# SurfaceEEG_E_V1_1.net
KiCad netlist of a schematic drawn in EAGLE
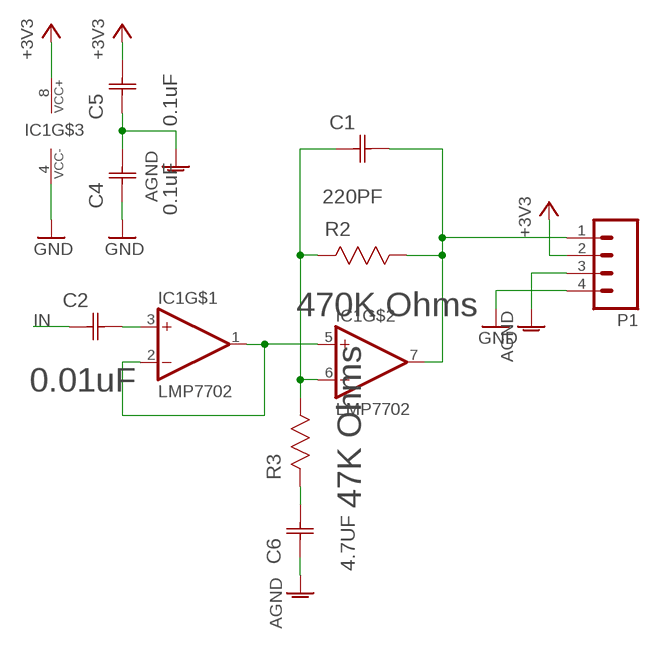
[diagram p0: schematic, sheet 1]

(export (version "E")
  (design (tool "Eeschema 10.0.6"))
  (components
    (comp (ref "C1")
      (value "220PF")
      (footprint "eagle-import:CAPC1608X90N")
      (fields (field (name "MPN") "0603ZC221KAT2A") (field (name "TOLERANCE") "±10%"))
      (libsource (lib "eagle-import") (part "0603ZC221KAT2A"))
    )
    (comp (ref "C2")
      (value "0.01uF")
      (footprint "eagle-import:CAPC1005X60N")
      (fields (field (name "MPN") "C0402C103J3RACTU") (field (name "TOLERANCE") "±5%"))
      (libsource (lib "eagle-import") (part "C0402C103J3RACTU"))
    )
    (comp (ref "C4")
      (value "0.1uF")
      (footprint "eagle-import:CAPC1005X60N")
      (fields (field (name "MPN") "04023C104KAT2A") (field (name "TOLERANCE") "±10%"))
      (libsource (lib "eagle-import") (part "04023C104KAT2A"))
    )
    (comp (ref "C5")
      (value "0.1uF")
      (footprint "eagle-import:CAPC1005X60N")
      (fields (field (name "MPN") "04023C104KAT2A") (field (name "TOLERANCE") "±10%"))
      (libsource (lib "eagle-import") (part "04023C104KAT2A"))
    )
    (comp (ref "C6")
      (value "4.7UF")
      (footprint "eagle-import:CAPC1608X90N")
      (fields (field (name "MPN") "06036D475MAT2A") (field (name "TOLERANCE") "±20%"))
      (libsource (lib "eagle-import") (part "06036D475MAT2A"))
    )
    (comp (ref "IC1")
      (value "LMP7702")
      (footprint "eagle-import:VSSOP8")
      (fields (field (name "MPN") "LMP7702MM/NOPB"))
      (libsource (lib "eagle-import") (part "LMP7702"))
    )
    (comp (ref "P1")
      (value "M04SMD")
      (footprint "eagle-import:1X04-SMD")
      (libsource (lib "eagle-import") (part "M04SMD"))
    )
    (comp (ref "R2")
      (value "470K Ohms")
      (footprint "eagle-import:RESC1608X60N")
      (fields (field (name "MPN") "RC0603FR-07470KL") (field (name "TOLERANCE") "±1%"))
      (libsource (lib "eagle-import") (part "RC0603FR-07470KL"))
    )
    (comp (ref "R3")
      (value "47K Ohms")
      (footprint "eagle-import:RESC1608X60N")
      (fields (field (name "MPN") "RC0603FR-0747KL") (field (name "TOLERANCE") "±1%"))
      (libsource (lib "eagle-import") (part "RC0603FR-0747KL"))
    )
  )
  (nets
    (net (code "1") (name "+3V3") (class "Default")
      (node (ref "C5") (pin "1") (pinfunction "C2_1") (pintype "passive"))
      (node (ref "IC1") (pin "8") (pinfunction "VCC+_8") (pintype "power_in"))
      (node (ref "P1") (pin "2") (pinfunction "2_2") (pintype "passive"))
    )
    (net (code "2") (name "/IN") (class "Default")
      (node (ref "C2") (pin "1") (pinfunction "C1_1") (pintype "passive"))
    )
    (net (code "3") (name "AGND") (class "Default")
      (node (ref "C4") (pin "1") (pinfunction "C2_1") (pintype "passive"))
      (node (ref "C5") (pin "2") (pinfunction "C1_2") (pintype "passive"))
      (node (ref "C6") (pin "1") (pinfunction "C1_1") (pintype "passive"))
      (node (ref "P1") (pin "3") (pinfunction "3_3") (pintype "passive"))
    )
    (net (code "4") (name "GND") (class "Default")
      (node (ref "C4") (pin "2") (pinfunction "C1_2") (pintype "passive"))
      (node (ref "IC1") (pin "4") (pinfunction "VCC-_4") (pintype "power_in"))
      (node (ref "P1") (pin "4") (pinfunction "4_4") (pintype "passive"))
    )
    (net (code "5") (name "Net-(C1-C1)") (class "Default")
      (node (ref "C1") (pin "1") (pinfunction "C1_1") (pintype "passive"))
      (node (ref "IC1") (pin "6") (pinfunction "IN-_6") (pintype "input"))
      (node (ref "R2") (pin "2") (pinfunction "R2_2") (pintype "passive"))
      (node (ref "R3") (pin "1") (pinfunction "R1_1") (pintype "passive"))
    )
    (net (code "6") (name "Net-(C1-C2)") (class "Default")
      (node (ref "C1") (pin "2") (pinfunction "C2_2") (pintype "passive"))
      (node (ref "IC1") (pin "7") (pinfunction "OUT_7") (pintype "output"))
      (node (ref "P1") (pin "1") (pinfunction "1_1") (pintype "passive"))
      (node (ref "R2") (pin "1") (pinfunction "R1_1") (pintype "passive"))
    )
    (net (code "7") (name "Net-(C2-C2)") (class "Default")
      (node (ref "C2") (pin "2") (pinfunction "C2_2") (pintype "passive"))
      (node (ref "IC1") (pin "3") (pinfunction "IN+_3") (pintype "input"))
    )
    (net (code "8") (name "Net-(C6-C2)") (class "Default")
      (node (ref "C6") (pin "2") (pinfunction "C2_2") (pintype "passive"))
      (node (ref "R3") (pin "2") (pinfunction "R2_2") (pintype "passive"))
    )
    (net (code "9") (name "Net-(IC1A-IN-)") (class "Default")
      (node (ref "IC1") (pin "1") (pinfunction "OUT_1") (pintype "output"))
      (node (ref "IC1") (pin "2") (pinfunction "IN-_2") (pintype "input"))
      (node (ref "IC1") (pin "5") (pinfunction "IN+_5") (pintype "input"))
    )
  )
)
